# AuxBoard030624.net
KiCad netlist of a schematic drawn in Altium Designer
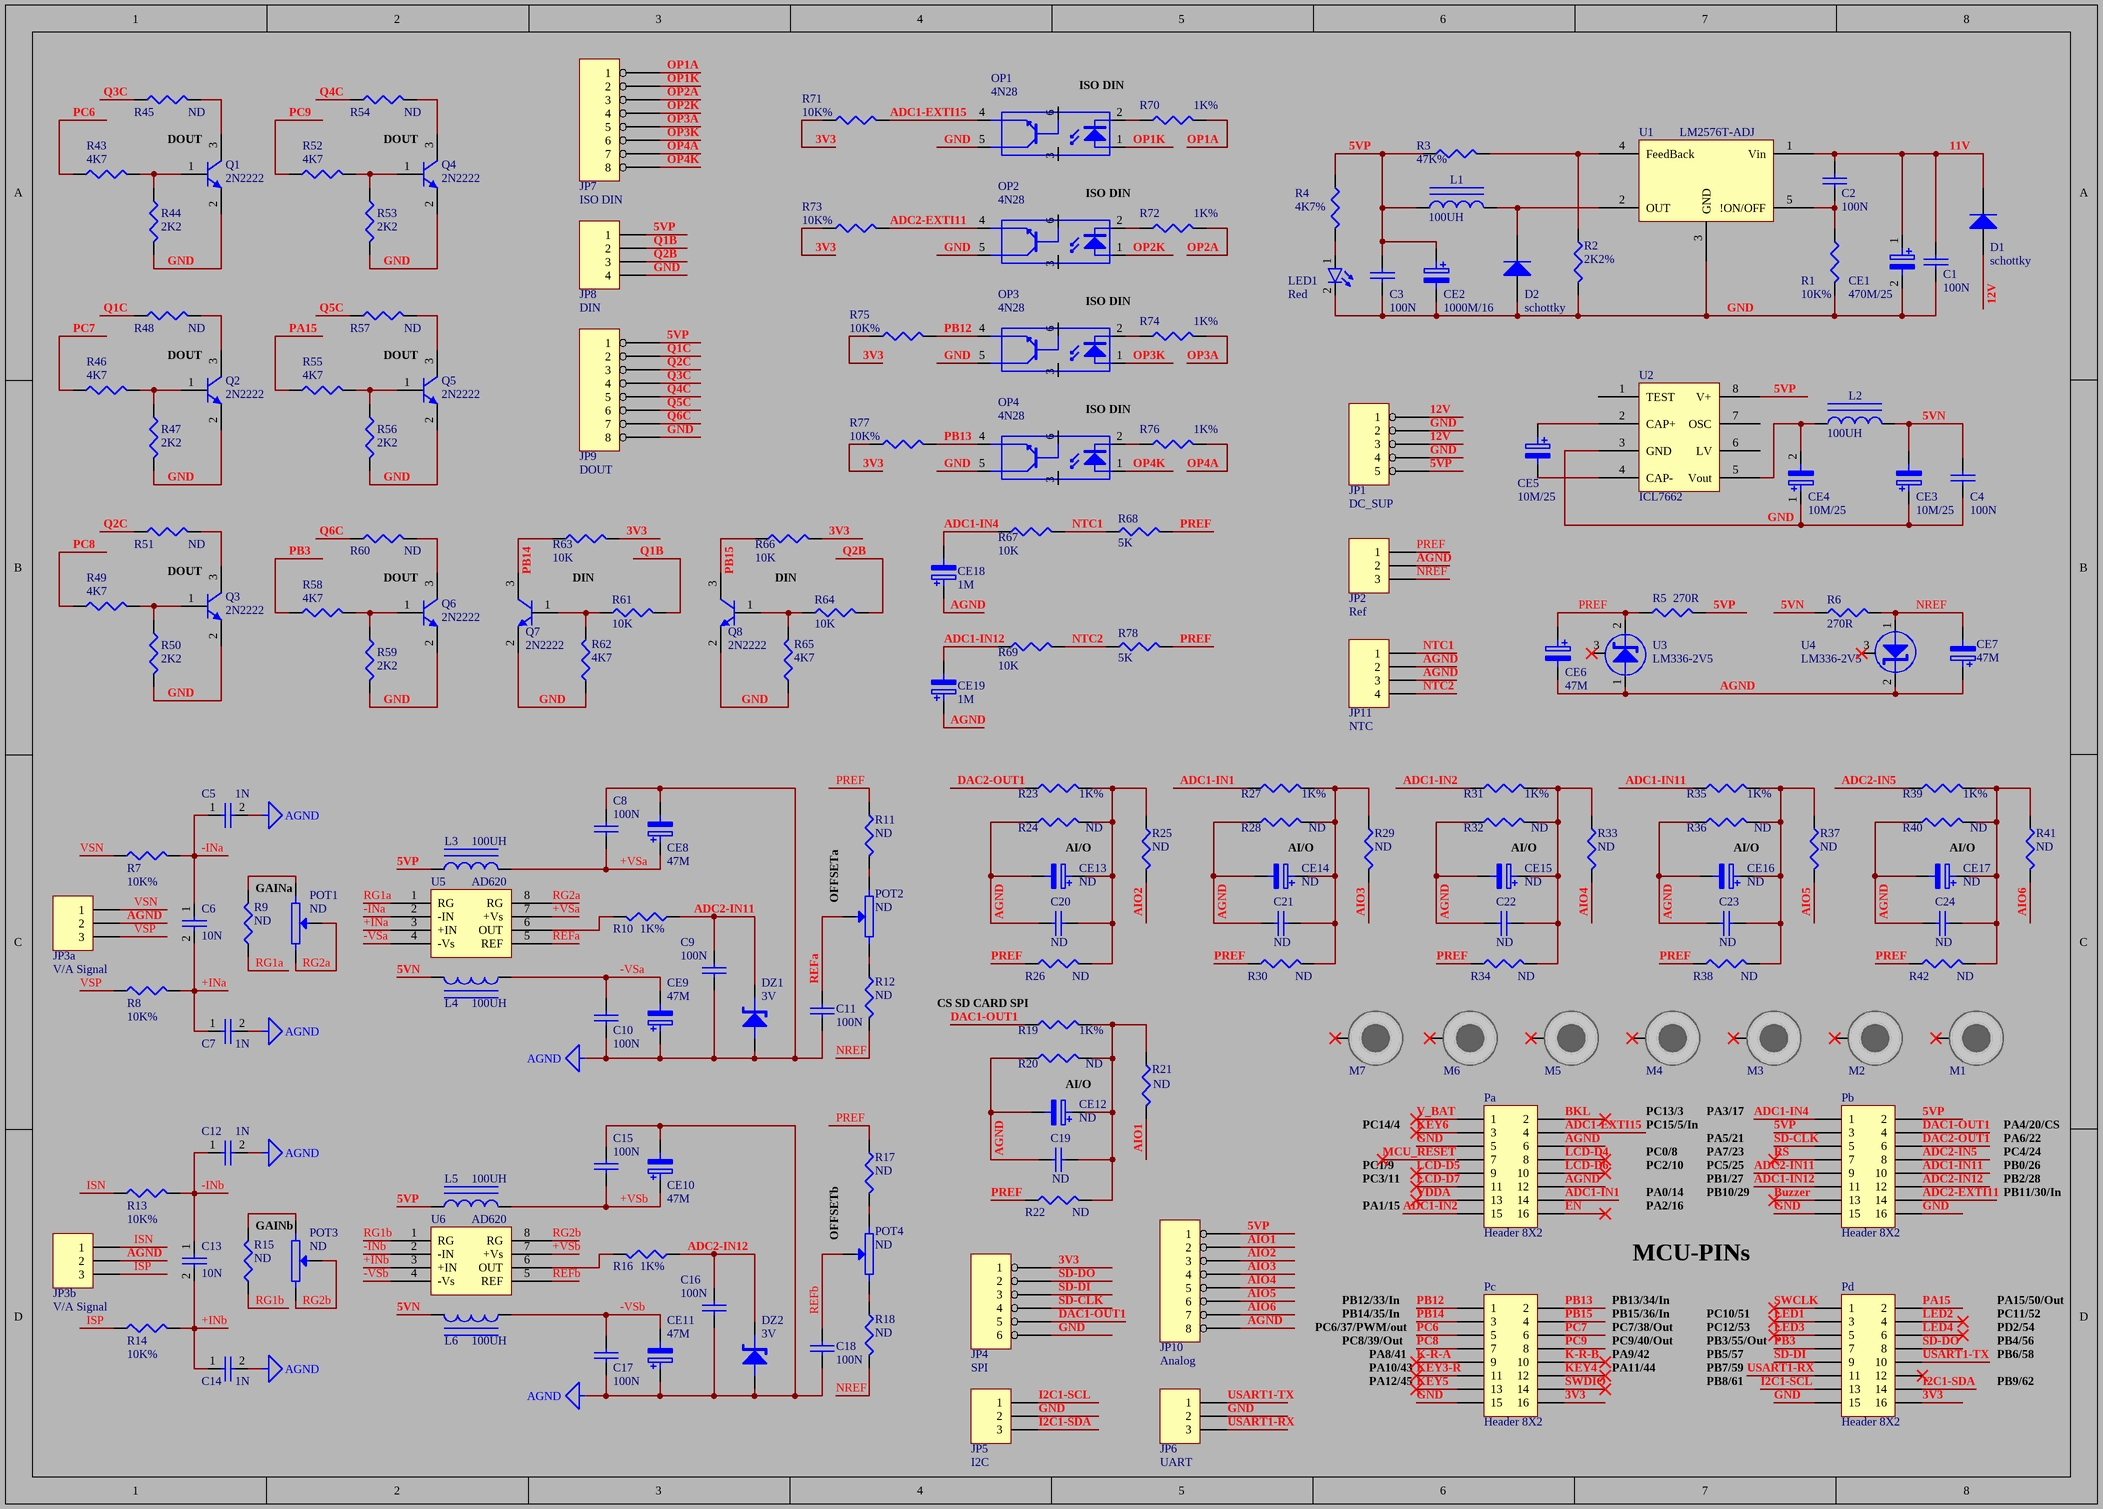
[diagram p0: AuxBoard030624.SchDoc]

(export (version "E")
  (design (tool "Eeschema 10.0.6"))
  (components
    (comp (ref "C1") (value "100N") (footprint "C2P") (libsource (lib "*") (part "C")))
    (comp (ref "C2") (value "100N") (footprint "SMD_CAP_1206.") (libsource (lib "*") (part "C")))
    (comp (ref "C3") (value "100N") (footprint "SMD_CAP_1206.") (libsource (lib "*") (part "C")))
    (comp (ref "C4") (value "100N") (footprint "SMD_CAP_1206.") (libsource (lib "*") (part "C")))
    (comp (ref "C5") (value "1N") (footprint "SMD_CAP_1206.") (libsource (lib "1402 Schlib 2020") (part "C")))
    (comp (ref "C6")
      (value "10N")
      (footprint "SMD_CAP_1206.")
      (libsource (lib "1402 Schlib 2020") (part "C"))
    )
    (comp (ref "C7") (value "1N") (footprint "SMD_CAP_1206.") (libsource (lib "1402 Schlib 2020") (part "C")))
    (comp (ref "C8")
      (value "100N")
      (footprint "SMD_CAP_1206.")
      (libsource (lib "1403 Schlib 2020") (part "C"))
    )
    (comp (ref "C9")
      (value "100N")
      (footprint "SMD_CAP_1206.")
      (libsource (lib "1403 Schlib 2020") (part "C"))
    )
    (comp (ref "C10")
      (value "100N")
      (footprint "SMD_CAP_1206.")
      (libsource (lib "1403 Schlib 2020") (part "C"))
    )
    (comp (ref "C11")
      (value "100N")
      (footprint "SMD_CAP_1206.")
      (libsource (lib "1403 Schlib 2020") (part "C"))
    )
    (comp (ref "C12")
      (value "1N")
      (footprint "SMD_CAP_1206.")
      (libsource (lib "1402 Schlib 2020") (part "C"))
    )
    (comp (ref "C13")
      (value "10N")
      (footprint "SMD_CAP_1206.")
      (libsource (lib "1402 Schlib 2020") (part "C"))
    )
    (comp (ref "C14")
      (value "1N")
      (footprint "SMD_CAP_1206.")
      (libsource (lib "1402 Schlib 2020") (part "C"))
    )
    (comp (ref "C15")
      (value "100N")
      (footprint "SMD_CAP_1206.")
      (libsource (lib "1403 Schlib 2020") (part "C"))
    )
    (comp (ref "C16")
      (value "100N")
      (footprint "SMD_CAP_1206.")
      (libsource (lib "1403 Schlib 2020") (part "C"))
    )
    (comp (ref "C17")
      (value "100N")
      (footprint "SMD_CAP_1206.")
      (libsource (lib "1403 Schlib 2020") (part "C"))
    )
    (comp (ref "C18")
      (value "100N")
      (footprint "SMD_CAP_1206.")
      (libsource (lib "1403 Schlib 2020") (part "C"))
    )
    (comp (ref "C19") (value "ND") (footprint "SMD_CAP_1206.") (libsource (lib "*") (part "C")))
    (comp (ref "C20") (value "ND") (footprint "SMD_CAP_1206.") (libsource (lib "*") (part "C")))
    (comp (ref "C21") (value "ND") (footprint "SMD_CAP_1206.") (libsource (lib "*") (part "C")))
    (comp (ref "C22") (value "ND") (footprint "SMD_CAP_1206.") (libsource (lib "*") (part "C")))
    (comp (ref "C23") (value "ND") (footprint "SMD_CAP_1206.") (libsource (lib "*") (part "C")))
    (comp (ref "C24") (value "ND") (footprint "SMD_CAP_1206.") (libsource (lib "*") (part "C")))
    (comp (ref "CE1") (value "470M/25") (footprint "CAP-E-6") (libsource (lib "*") (part "E")))
    (comp (ref "CE2") (value "1000M/16") (footprint "CAP-E-6") (libsource (lib "") (part "E_1")))
    (comp (ref "CE3") (value "10M/25") (footprint "CAP-E-3") (libsource (lib "") (part "E_1")))
    (comp (ref "CE4") (value "10M/25") (footprint "CAP-E-3") (libsource (lib "*") (part "E")))
    (comp (ref "CE5") (value "10M/25") (footprint "CAP-E-3") (libsource (lib "") (part "E_1")))
    (comp (ref "CE6") (value "47M") (footprint "CAP-E-4") (libsource (lib "1403 Schlib 2020") (part "E")))
    (comp (ref "CE7") (value "47M") (footprint "CAP-E-4") (libsource (lib "1403 Schlib 2020") (part "E")))
    (comp (ref "CE8") (value "47M") (footprint "CAP-E-4") (libsource (lib "1403 Schlib 2020") (part "E")))
    (comp (ref "CE9") (value "47M") (footprint "CAP-E-4") (libsource (lib "1403 Schlib 2020") (part "E")))
    (comp (ref "CE10") (value "47M") (footprint "CAP-E-4") (libsource (lib "1403 Schlib 2020") (part "E")))
    (comp (ref "CE11") (value "47M") (footprint "CAP-E-4") (libsource (lib "1403 Schlib 2020") (part "E")))
    (comp (ref "CE12") (value "ND") (footprint "CAP-E-3") (libsource (lib "") (part "E_1")))
    (comp (ref "CE13") (value "ND") (footprint "CAP-E-3") (libsource (lib "") (part "E_1")))
    (comp (ref "CE14") (value "ND") (footprint "CAP-E-3") (libsource (lib "") (part "E_1")))
    (comp (ref "CE15") (value "ND") (footprint "CAP-E-3") (libsource (lib "") (part "E_1")))
    (comp (ref "CE16") (value "ND") (footprint "CAP-E-3") (libsource (lib "") (part "E_1")))
    (comp (ref "CE17") (value "ND") (footprint "CAP-E-3") (libsource (lib "") (part "E_1")))
    (comp (ref "CE18") (value "1M") (footprint "CAP-E-2") (libsource (lib "") (part "E_1")))
    (comp (ref "CE19") (value "1M") (footprint "CAP-E-2") (libsource (lib "") (part "E_1")))
    (comp (ref "D1")
      (value "schottky")
      (footprint "SMA-M")
      (description "Default Diode")
      (fields (field (name "PUBLISHER") "Altium Limited"))
      (libsource (lib "Miscellaneous Devices") (part "Diode"))
    )
    (comp (ref "D2")
      (value "schottky")
      (footprint "SMA-M")
      (description "Default Diode")
      (fields (field (name "PUBLISHER") "Altium Limited"))
      (libsource (lib "Miscellaneous Devices") (part "Diode"))
    )
    (comp (ref "DZ1") (value "3V") (footprint "D4P") (libsource (lib "1402 Schlib 2020") (part "Z")))
    (comp (ref "DZ2") (value "3V") (footprint "D4P") (libsource (lib "1402 Schlib 2020") (part "Z")))
    (comp (ref "JP1")
      (value "DC_SUP")
      (footprint "dsip 5 right")
      (libsource (lib "1402 Schlib 2020") (part "HEADER 5"))
    )
    (comp (ref "JP2")
      (value "Ref")
      (footprint "dsip 3 right")
      (description "Header, 3-Pin")
      (fields (field (name "PUBLISHER") "Altium Limited"))
      (libsource (lib "1402 Schlib 2020") (part "Header 3"))
    )
    (comp (ref "JP3a")
      (value "V/A Signal")
      (footprint "dsip 3 right")
      (description "Header, 3-Pin")
      (fields (field (name "PUBLISHER") "Altium Limited"))
      (libsource (lib "1402 Schlib 2020") (part "Header 3"))
    )
    (comp (ref "JP3b")
      (value "V/A Signal")
      (footprint "dsip 3 right")
      (description "Header, 3-Pin")
      (fields (field (name "PUBLISHER") "Altium Limited"))
      (libsource (lib "1402 Schlib 2020") (part "Header 3"))
    )
    (comp (ref "JP4")
      (value "SPI")
      (footprint "SIP 6 Right")
      (libsource (lib "1402 Schlib 2020") (part "HEADER 6"))
    )
    (comp (ref "JP5")
      (value "I2C")
      (footprint "SIP 3 Right")
      (description "Header, 3-Pin")
      (fields (field (name "PUBLISHER") "Altium Limited"))
      (libsource (lib "1402 Schlib 2020") (part "Header 3"))
    )
    (comp (ref "JP6")
      (value "UART")
      (footprint "SIP 3 Right")
      (description "Header, 3-Pin")
      (fields (field (name "PUBLISHER") "Altium Limited"))
      (libsource (lib "1402 Schlib 2020") (part "Header 3"))
    )
    (comp (ref "JP7")
      (value "ISO DIN")
      (footprint "dsip 8 right")
      (libsource (lib "1402 Schlib 2020") (part "HEADER 8"))
    )
    (comp (ref "JP8")
      (value "DIN")
      (footprint "dsip 4 right")
      (description "Header, 4-Pin")
      (fields (field (name "PUBLISHER") "Altium Limited"))
      (libsource (lib "1402 Schlib 2020") (part "Header 4"))
    )
    (comp (ref "JP9")
      (value "DOUT")
      (footprint "dsip 8 right")
      (libsource (lib "1402 Schlib 2020") (part "HEADER 8"))
    )
    (comp (ref "JP10")
      (value "Analog")
      (footprint "dsip 8 right")
      (libsource (lib "1402 Schlib 2020") (part "HEADER 8"))
    )
    (comp (ref "JP11")
      (value "NTC")
      (footprint "dsip 4 right")
      (description "Header, 4-Pin")
      (fields (field (name "PUBLISHER") "Altium Limited"))
      (libsource (lib "1402 Schlib 2020") (part "Header 4"))
    )
    (comp (ref "L1") (value "100UH") (footprint "INDUCTOR-ylw") (libsource (lib "*") (part "INDUCTOR IRON")))
    (comp (ref "L2") (value "100UH") (footprint "r4p") (libsource (lib "*") (part "INDUCTOR IRON")))
    (comp (ref "L3") (value "100UH") (footprint "r4p") (libsource (lib "*") (part "INDUCTOR IRON")))
    (comp (ref "L4") (value "100UH") (footprint "r4p") (libsource (lib "") (part "INDUCTOR IRON_1")))
    (comp (ref "L5") (value "100UH") (footprint "r4p") (libsource (lib "*") (part "INDUCTOR IRON")))
    (comp (ref "L6") (value "100UH") (footprint "r4p") (libsource (lib "") (part "INDUCTOR IRON_1")))
    (comp (ref "LED1")
      (value "Red")
      (footprint "LED_SMD_1206")
      (description "LED")
      (fields (field (name "COLOR") "Red") (field (name "DESIGNER") "Saeid Jorablo"))
      (libsource (lib "My Library") (part "LED"))
    )
    (comp (ref "M1")
      (value "Comment")
      (footprint "Stud-hole")
      (description "SCREW mouting, M1.6, 1.6mm diameter and 3.2mm PanHead")
      (libsource (lib "DotexGroup_LIB") (part "SCMH_M1P6"))
    )
    (comp (ref "M2")
      (value "Comment")
      (footprint "Stud-hole")
      (description "SCREW mouting, M1.6, 1.6mm diameter and 3.2mm PanHead")
      (libsource (lib "DotexGroup_LIB") (part "SCMH_M1P6"))
    )
    (comp (ref "M3")
      (value "Comment")
      (footprint "Stud-hole")
      (description "SCREW mouting, M1.6, 1.6mm diameter and 3.2mm PanHead")
      (libsource (lib "DotexGroup_LIB") (part "SCMH_M1P6"))
    )
    (comp (ref "M4")
      (value "Comment")
      (footprint "Stud-hole")
      (description "SCREW mouting, M1.6, 1.6mm diameter and 3.2mm PanHead")
      (libsource (lib "DotexGroup_LIB") (part "SCMH_M1P6"))
    )
    (comp (ref "M5")
      (value "Comment")
      (footprint "Stud-hole")
      (description "SCREW mouting, M1.6, 1.6mm diameter and 3.2mm PanHead")
      (libsource (lib "DotexGroup_LIB") (part "SCMH_M1P6"))
    )
    (comp (ref "M6")
      (value "Comment")
      (footprint "Stud-hole")
      (description "SCREW mouting, M1.6, 1.6mm diameter and 3.2mm PanHead")
      (libsource (lib "DotexGroup_LIB") (part "SCMH_M1P6"))
    )
    (comp (ref "M7")
      (value "Comment")
      (footprint "Stud-hole")
      (description "SCREW mouting, M1.6, 1.6mm diameter and 3.2mm PanHead")
      (libsource (lib "DotexGroup_LIB") (part "SCMH_M1P6"))
    )
    (comp (ref "OP1")
      (value "4N28")
      (footprint "DIP6")
      (libsource (lib "1402 Schlib 2020") (part "OPTODIP6"))
    )
    (comp (ref "OP2")
      (value "4N28")
      (footprint "DIP6")
      (libsource (lib "1402 Schlib 2020") (part "OPTODIP6"))
    )
    (comp (ref "OP3")
      (value "4N28")
      (footprint "DIP6")
      (libsource (lib "1402 Schlib 2020") (part "OPTODIP6"))
    )
    (comp (ref "OP4")
      (value "4N28")
      (footprint "DIP6")
      (libsource (lib "1402 Schlib 2020") (part "OPTODIP6"))
    )
    (comp (ref "Pa")
      (value "Header 8X2")
      (footprint "HDR2X8")
      (description "Header, 8-Pin, Dual row")
      (fields (field (name "PUBLISHER") "Altium Limited"))
      (libsource (lib "Miscellaneous Connectors") (part "Header 8X2"))
    )
    (comp (ref "Pb")
      (value "Header 8X2")
      (footprint "HDR2X8")
      (description "Header, 8-Pin, Dual row")
      (fields (field (name "PUBLISHER") "Altium Limited"))
      (libsource (lib "Miscellaneous Connectors") (part "Header 8X2"))
    )
    (comp (ref "Pc")
      (value "Header 8X2")
      (footprint "HDR2X8")
      (description "Header, 8-Pin, Dual row")
      (fields (field (name "PUBLISHER") "Altium Limited"))
      (libsource (lib "Miscellaneous Connectors") (part "Header 8X2"))
    )
    (comp (ref "Pd")
      (value "Header 8X2")
      (footprint "HDR2X8")
      (description "Header, 8-Pin, Dual row")
      (fields (field (name "PUBLISHER") "Altium Limited"))
      (libsource (lib "Miscellaneous Connectors") (part "Header 8X2"))
    )
    (comp (ref "POT1")
      (value "ND")
      (footprint "pot multi turn")
      (libsource (lib "1402 Schlib 2020") (part "POT2"))
    )
    (comp (ref "POT2")
      (value "ND")
      (footprint "pot multi turn")
      (libsource (lib "1402 Schlib 2020") (part "POT2"))
    )
    (comp (ref "POT3")
      (value "ND")
      (footprint "pot multi turn")
      (libsource (lib "1402 Schlib 2020") (part "POT2"))
    )
    (comp (ref "POT4")
      (value "ND")
      (footprint "pot multi turn")
      (libsource (lib "1402 Schlib 2020") (part "POT2"))
    )
    (comp (ref "Q1")
      (value "2N2222")
      (footprint "2N2222")
      (description "NPN")
      (fields (field (name "PUBLISHER") "Altium Limited"))
      (libsource (lib "1402 Schlib 2020") (part "1FW"))
    )
    (comp (ref "Q2")
      (value "2N2222")
      (footprint "2N2222")
      (description "NPN")
      (fields (field (name "PUBLISHER") "Altium Limited"))
      (libsource (lib "1402 Schlib 2020") (part "1FW"))
    )
    (comp (ref "Q3")
      (value "2N2222")
      (footprint "2N2222")
      (description "NPN")
      (fields (field (name "PUBLISHER") "Altium Limited"))
      (libsource (lib "1402 Schlib 2020") (part "1FW"))
    )
    (comp (ref "Q4")
      (value "2N2222")
      (footprint "2N2222")
      (description "NPN")
      (fields (field (name "PUBLISHER") "Altium Limited"))
      (libsource (lib "1402 Schlib 2020") (part "1FW"))
    )
    (comp (ref "Q5")
      (value "2N2222")
      (footprint "2N2222")
      (description "NPN")
      (fields (field (name "PUBLISHER") "Altium Limited"))
      (libsource (lib "1402 Schlib 2020") (part "1FW"))
    )
    (comp (ref "Q6")
      (value "2N2222")
      (footprint "2N2222")
      (description "NPN")
      (fields (field (name "PUBLISHER") "Altium Limited"))
      (libsource (lib "1402 Schlib 2020") (part "1FW"))
    )
    (comp (ref "Q7")
      (value "2N2222")
      (footprint "2N2222")
      (description "NPN")
      (fields (field (name "PUBLISHER") "Altium Limited"))
      (libsource (lib "1402 Schlib 2020") (part "1FW"))
    )
    (comp (ref "Q8")
      (value "2N2222")
      (footprint "2N2222")
      (description "NPN")
      (fields (field (name "PUBLISHER") "Altium Limited"))
      (libsource (lib "1402 Schlib 2020") (part "1FW"))
    )
    (comp (ref "R1") (value "10K%") (footprint "RES_1206") (libsource (lib "*") (part "R")))
    (comp (ref "R2") (value "2K2%") (footprint "RES_1206") (libsource (lib "*") (part "R")))
    (comp (ref "R3") (value "47K%") (footprint "RES_1206") (libsource (lib "*") (part "R")))
    (comp (ref "R4") (value "4K7%") (footprint "RES_1206") (libsource (lib "*") (part "R")))
    (comp (ref "R5") (value "270R") (footprint "RES_1206") (libsource (lib "*") (part "R")))
    (comp (ref "R6") (value "270R") (footprint "RES_1206") (libsource (lib "*") (part "R")))
    (comp (ref "R7") (value "10K%") (footprint "R4P") (libsource (lib "*") (part "R")))
    (comp (ref "R8") (value "10K%") (footprint "R4P") (libsource (lib "*") (part "R")))
    (comp (ref "R9") (value "ND") (footprint "R4P") (libsource (lib "*") (part "R")))
    (comp (ref "R10") (value "1K%") (footprint "RES_1206") (libsource (lib "*") (part "R")))
    (comp (ref "R11") (value "ND") (footprint "RES_1206") (libsource (lib "*") (part "R")))
    (comp (ref "R12") (value "ND") (footprint "RES_1206") (libsource (lib "*") (part "R")))
    (comp (ref "R13") (value "10K%") (footprint "R4P") (libsource (lib "*") (part "R")))
    (comp (ref "R14") (value "10K%") (footprint "R4P") (libsource (lib "*") (part "R")))
    (comp (ref "R15") (value "ND") (footprint "R4P") (libsource (lib "*") (part "R")))
    (comp (ref "R16") (value "1K%") (footprint "RES_1206") (libsource (lib "*") (part "R")))
    (comp (ref "R17") (value "ND") (footprint "RES_1206") (libsource (lib "*") (part "R")))
    (comp (ref "R18") (value "ND") (footprint "RES_1206") (libsource (lib "*") (part "R")))
    (comp (ref "R19") (value "1K%") (footprint "RES_1206") (libsource (lib "*") (part "R")))
    (comp (ref "R20") (value "ND") (footprint "RES_1206") (libsource (lib "*") (part "R")))
    (comp (ref "R21") (value "ND") (footprint "RES_1206") (libsource (lib "*") (part "R")))
    (comp (ref "R22") (value "ND") (footprint "RES_1206") (libsource (lib "*") (part "R")))
    (comp (ref "R23") (value "1K%") (footprint "RES_1206") (libsource (lib "*") (part "R")))
    (comp (ref "R24") (value "ND") (footprint "RES_1206") (libsource (lib "*") (part "R")))
    (comp (ref "R25") (value "ND") (footprint "RES_1206") (libsource (lib "*") (part "R")))
    (comp (ref "R26") (value "ND") (footprint "RES_1206") (libsource (lib "*") (part "R")))
    (comp (ref "R27") (value "1K%") (footprint "RES_1206") (libsource (lib "*") (part "R")))
    (comp (ref "R28") (value "ND") (footprint "RES_1206") (libsource (lib "*") (part "R")))
    (comp (ref "R29") (value "ND") (footprint "RES_1206") (libsource (lib "*") (part "R")))
    (comp (ref "R30") (value "ND") (footprint "RES_1206") (libsource (lib "*") (part "R")))
    (comp (ref "R31") (value "1K%") (footprint "RES_1206") (libsource (lib "*") (part "R")))
    (comp (ref "R32") (value "ND") (footprint "RES_1206") (libsource (lib "*") (part "R")))
    (comp (ref "R33") (value "ND") (footprint "RES_1206") (libsource (lib "*") (part "R")))
    (comp (ref "R34") (value "ND") (footprint "RES_1206") (libsource (lib "*") (part "R")))
    (comp (ref "R35") (value "1K%") (footprint "RES_1206") (libsource (lib "*") (part "R")))
    (comp (ref "R36") (value "ND") (footprint "RES_1206") (libsource (lib "*") (part "R")))
    (comp (ref "R37") (value "ND") (footprint "RES_1206") (libsource (lib "*") (part "R")))
    (comp (ref "R38") (value "ND") (footprint "RES_1206") (libsource (lib "*") (part "R")))
    (comp (ref "R39") (value "1K%") (footprint "RES_1206") (libsource (lib "*") (part "R")))
    (comp (ref "R40") (value "ND") (footprint "RES_1206") (libsource (lib "*") (part "R")))
    (comp (ref "R41") (value "ND") (footprint "RES_1206") (libsource (lib "*") (part "R")))
    (comp (ref "R42") (value "ND") (footprint "RES_1206") (libsource (lib "*") (part "R")))
    (comp (ref "R43") (value "4K7") (footprint "RES_1206") (libsource (lib "*") (part "R")))
    (comp (ref "R44") (value "2K2") (footprint "RES_1206") (libsource (lib "*") (part "R")))
    (comp (ref "R45") (value "ND") (footprint "RES_1206") (libsource (lib "*") (part "R")))
    (comp (ref "R46") (value "4K7") (footprint "RES_1206") (libsource (lib "*") (part "R")))
    (comp (ref "R47") (value "2K2") (footprint "RES_1206") (libsource (lib "*") (part "R")))
    (comp (ref "R48") (value "ND") (footprint "RES_1206") (libsource (lib "*") (part "R")))
    (comp (ref "R49") (value "4K7") (footprint "RES_1206") (libsource (lib "*") (part "R")))
    (comp (ref "R50") (value "2K2") (footprint "RES_1206") (libsource (lib "*") (part "R")))
    (comp (ref "R51") (value "ND") (footprint "RES_1206") (libsource (lib "*") (part "R")))
    (comp (ref "R52") (value "4K7") (footprint "RES_1206") (libsource (lib "*") (part "R")))
    (comp (ref "R53") (value "2K2") (footprint "RES_1206") (libsource (lib "*") (part "R")))
    (comp (ref "R54") (value "ND") (footprint "RES_1206") (libsource (lib "*") (part "R")))
    (comp (ref "R55") (value "4K7") (footprint "RES_1206") (libsource (lib "*") (part "R")))
    (comp (ref "R56") (value "2K2") (footprint "RES_1206") (libsource (lib "*") (part "R")))
    (comp (ref "R57") (value "ND") (footprint "RES_1206") (libsource (lib "*") (part "R")))
    (comp (ref "R58") (value "4K7") (footprint "RES_1206") (libsource (lib "*") (part "R")))
    (comp (ref "R59") (value "2K2") (footprint "RES_1206") (libsource (lib "*") (part "R")))
    (comp (ref "R60") (value "ND") (footprint "RES_1206") (libsource (lib "*") (part "R")))
    (comp (ref "R61") (value "10K") (footprint "RES_1206") (libsource (lib "*") (part "R")))
    (comp (ref "R62") (value "4K7") (footprint "RES_1206") (libsource (lib "*") (part "R")))
    (comp (ref "R63") (value "10K") (footprint "RES_1206") (libsource (lib "*") (part "R")))
    (comp (ref "R64") (value "10K") (footprint "RES_1206") (libsource (lib "*") (part "R")))
    (comp (ref "R65") (value "4K7") (footprint "RES_1206") (libsource (lib "*") (part "R")))
    (comp (ref "R66") (value "10K") (footprint "RES_1206") (libsource (lib "*") (part "R")))
    (comp (ref "R67") (value "10K") (footprint "RES_1206") (libsource (lib "*") (part "R")))
    (comp (ref "R68") (value "5K") (footprint "RES_1206") (libsource (lib "*") (part "R")))
    (comp (ref "R69") (value "10K") (footprint "RES_1206") (libsource (lib "*") (part "R")))
    (comp (ref "R70") (value "1K%") (footprint "RES_1206") (libsource (lib "*") (part "R")))
    (comp (ref "R71") (value "10K%") (footprint "RES_1206") (libsource (lib "*") (part "R")))
    (comp (ref "R72") (value "1K%") (footprint "RES_1206") (libsource (lib "*") (part "R")))
    (comp (ref "R73") (value "10K%") (footprint "RES_1206") (libsource (lib "*") (part "R")))
    (comp (ref "R74") (value "1K%") (footprint "RES_1206") (libsource (lib "*") (part "R")))
    (comp (ref "R75") (value "10K%") (footprint "RES_1206") (libsource (lib "*") (part "R")))
    (comp (ref "R76") (value "1K%") (footprint "RES_1206") (libsource (lib "*") (part "R")))
    (comp (ref "R77") (value "10K%") (footprint "RES_1206") (libsource (lib "*") (part "R")))
    (comp (ref "R78") (value "5K") (footprint "RES_1206") (libsource (lib "*") (part "R")))
    (comp (ref "U1") (value "LM2576T-ADJ") (footprint "D2PACK_TO263-5") (libsource (lib "*") (part "LM2576")))
    (comp (ref "U2")
      (value "ICL7662")
      (footprint "DIP8")
      (libsource (lib "1402 Schlib 2020") (part "ICL7662"))
    )
    (comp (ref "U3")
      (value "LM336-2V5")
      (footprint "lm336")
      (libsource (lib "1403 Schlib 2020") (part "LM336"))
    )
    (comp (ref "U4")
      (value "LM336-2V5")
      (footprint "lm336")
      (libsource (lib "1403 Schlib 2020") (part "LM336"))
    )
    (comp (ref "U5") (value "AD620") (footprint "DIP8") (libsource (lib "1402 Schlib 2020") (part "AD620")))
    (comp (ref "U6") (value "AD620") (footprint "DIP8") (libsource (lib "1402 Schlib 2020") (part "AD620")))
  )
  (nets
    (net (code "1") (name "/+INa") (class "Default")
      (node (ref "C6") (pin "2") (pintype "passive"))
      (node (ref "C7") (pin "1") (pintype "passive"))
      (node (ref "R8") (pin "2") (pintype "passive"))
      (node (ref "U5") (pin "3") (pinfunction "+IN_3") (pintype "passive"))
    )
    (net (code "2") (name "/+INb") (class "Default")
      (node (ref "C13") (pin "2") (pintype "passive"))
      (node (ref "C14") (pin "1") (pintype "passive"))
      (node (ref "R14") (pin "2") (pintype "passive"))
      (node (ref "U6") (pin "3") (pinfunction "+IN_3") (pintype "passive"))
    )
    (net (code "3") (name "/+VSa") (class "Default")
      (node (ref "C8") (pin "2") (pintype "passive"))
      (node (ref "CE8") (pin "1") (pintype "passive"))
      (node (ref "L3") (pin "2") (pinfunction "2_2") (pintype "passive"))
      (node (ref "U5") (pin "7") (pinfunction "+Vs_7") (pintype "passive"))
    )
    (net (code "4") (name "/+VSb") (class "Default")
      (node (ref "C15") (pin "2") (pintype "passive"))
      (node (ref "CE10") (pin "1") (pintype "passive"))
      (node (ref "L5") (pin "2") (pinfunction "2_2") (pintype "passive"))
      (node (ref "U6") (pin "7") (pinfunction "+Vs_7") (pintype "passive"))
    )
    (net (code "5") (name "/-INa") (class "Default")
      (node (ref "C5") (pin "1") (pintype "passive"))
      (node (ref "C6") (pin "1") (pintype "passive"))
      (node (ref "R7") (pin "2") (pintype "passive"))
      (node (ref "U5") (pin "2") (pinfunction "-IN_2") (pintype "passive"))
    )
    (net (code "6") (name "/-INb") (class "Default")
      (node (ref "C12") (pin "1") (pintype "passive"))
      (node (ref "C13") (pin "1") (pintype "passive"))
      (node (ref "R13") (pin "2") (pintype "passive"))
      (node (ref "U6") (pin "2") (pinfunction "-IN_2") (pintype "passive"))
    )
    (net (code "7") (name "/-VSa") (class "Default")
      (node (ref "C10") (pin "1") (pintype "passive"))
      (node (ref "CE9") (pin "2") (pintype "passive"))
      (node (ref "L4") (pin "2") (pinfunction "2_2") (pintype "passive"))
      (node (ref "U5") (pin "4") (pinfunction "-Vs_4") (pintype "passive"))
    )
    (net (code "8") (name "/-VSb") (class "Default")
      (node (ref "C17") (pin "1") (pintype "passive"))
      (node (ref "CE11") (pin "2") (pintype "passive"))
      (node (ref "L6") (pin "2") (pinfunction "2_2") (pintype "passive"))
      (node (ref "U6") (pin "4") (pinfunction "-Vs_4") (pintype "passive"))
    )
    (net (code "9") (name "/3V3") (class "Default")
      (node (ref "JP4") (pin "1") (pinfunction "1_1") (pintype "passive"))
      (node (ref "Pc") (pin "16") (pinfunction "16_16") (pintype "passive"))
      (node (ref "Pd") (pin "16") (pinfunction "16_16") (pintype "passive"))
      (node (ref "R63") (pin "1") (pintype "passive"))
      (node (ref "R66") (pin "1") (pintype "passive"))
      (node (ref "R71") (pin "2") (pintype "passive"))
      (node (ref "R73") (pin "2") (pintype "passive"))
      (node (ref "R75") (pin "2") (pintype "passive"))
      (node (ref "R77") (pin "2") (pintype "passive"))
    )
    (net (code "10") (name "/5VN") (class "Default")
      (node (ref "C4") (pin "1") (pintype "passive"))
      (node (ref "CE3") (pin "2") (pintype "passive"))
      (node (ref "L2") (pin "2") (pinfunction "2_2") (pintype "passive"))
      (node (ref "L4") (pin "1") (pinfunction "1_1") (pintype "passive"))
      (node (ref "L6") (pin "1") (pinfunction "1_1") (pintype "passive"))
      (node (ref "R6") (pin "2") (pintype "passive"))
    )
    (net (code "11") (name "/5VP") (class "Default")
      (node (ref "C3") (pin "1") (pintype "passive"))
      (node (ref "CE2") (pin "1") (pintype "passive"))
      (node (ref "JP1") (pin "5") (pinfunction "5_5") (pintype "passive"))
      (node (ref "JP10") (pin "1") (pinfunction "1_1") (pintype "passive"))
      (node (ref "JP8") (pin "1") (pinfunction "1_1") (pintype "passive"))
      (node (ref "JP9") (pin "1") (pinfunction "1_1") (pintype "passive"))
      (node (ref "L1") (pin "1") (pinfunction "1_1") (pintype "passive"))
      (node (ref "L3") (pin "1") (pinfunction "1_1") (pintype "passive"))
      (node (ref "L5") (pin "1") (pinfunction "1_1") (pintype "passive"))
      (node (ref "Pb") (pin "2") (pinfunction "2_2") (pintype "passive"))
      (node (ref "Pb") (pin "3") (pinfunction "3_3") (pintype "passive"))
      (node (ref "R3") (pin "1") (pintype "passive"))
      (node (ref "R4") (pin "1") (pintype "passive"))
      (node (ref "R5") (pin "2") (pintype "passive"))
      (node (ref "U2") (pin "8") (pinfunction "V+_8") (pintype "passive"))
    )
    (net (code "12") (name "/11V") (class "Default")
      (node (ref "C1") (pin "1") (pintype "passive"))
      (node (ref "C2") (pin "1") (pintype "passive"))
      (node (ref "CE1") (pin "1") (pintype "passive"))
      (node (ref "D1") (pin "2") (pinfunction "K_2") (pintype "passive"))
      (node (ref "U1") (pin "1") (pinfunction "Vin_1") (pintype "passive"))
    )
    (net (code "13") (name "/12V") (class "Default")
      (node (ref "D1") (pin "1") (pinfunction "A_1") (pintype "passive"))
      (node (ref "JP1") (pin "1") (pinfunction "1_1") (pintype "passive"))
      (node (ref "JP1") (pin "3") (pinfunction "3_3") (pintype "passive"))
    )
    (net (code "14") (name "/ADC1-EXTI15") (class "Default")
      (node (ref "OP1") (pin "4") (pinfunction "E_4") (pintype "passive"))
      (node (ref "Pa") (pin "4") (pinfunction "4_4") (pintype "passive"))
      (node (ref "R71") (pin "1") (pintype "passive"))
    )
    (net (code "15") (name "/ADC1-IN1") (class "Default")
      (node (ref "Pa") (pin "14") (pinfunction "14_14") (pintype "passive"))
      (node (ref "R27") (pin "1") (pintype "passive"))
    )
    (net (code "16") (name "/ADC1-IN2") (class "Default")
      (node (ref "Pa") (pin "15") (pinfunction "15_15") (pintype "passive"))
      (node (ref "R31") (pin "1") (pintype "passive"))
    )
    (net (code "17") (name "/ADC1-IN4") (class "Default")
      (node (ref "CE18") (pin "2") (pintype "passive"))
      (node (ref "Pb") (pin "1") (pinfunction "1_1") (pintype "passive"))
      (node (ref "R67") (pin "2") (pintype "passive"))
    )
    (net (code "18") (name "/ADC1-IN11") (class "Default")
      (node (ref "Pb") (pin "10") (pinfunction "10_10") (pintype "passive"))
      (node (ref "R35") (pin "1") (pintype "passive"))
    )
    (net (code "19") (name "/ADC1-IN12") (class "Default")
      (node (ref "CE19") (pin "2") (pintype "passive"))
      (node (ref "Pb") (pin "11") (pinfunction "11_11") (pintype "passive"))
      (node (ref "R69") (pin "2") (pintype "passive"))
    )
    (net (code "20") (name "/ADC2-EXTI11") (class "Default")
      (node (ref "OP2") (pin "4") (pinfunction "E_4") (pintype "passive"))
      (node (ref "Pb") (pin "14") (pinfunction "14_14") (pintype "passive"))
      (node (ref "R73") (pin "1") (pintype "passive"))
    )
    (net (code "21") (name "/ADC2-IN5") (class "Default")
      (node (ref "Pb") (pin "8") (pinfunction "8_8") (pintype "passive"))
      (node (ref "R39") (pin "1") (pintype "passive"))
    )
    (net (code "22") (name "/ADC2-IN11") (class "Default")
      (node (ref "C9") (pin "1") (pintype "passive"))
      (node (ref "DZ1") (pin "2") (pinfunction "K_2") (pintype "passive"))
      (node (ref "Pb") (pin "9") (pinfunction "9_9") (pintype "passive"))
      (node (ref "R10") (pin "1") (pintype "passive"))
    )
    (net (code "23") (name "/ADC2-IN12") (class "Default")
      (node (ref "C16") (pin "1") (pintype "passive"))
      (node (ref "DZ2") (pin "2") (pinfunction "K_2") (pintype "passive"))
      (node (ref "Pb") (pin "12") (pinfunction "12_12") (pintype "passive"))
      (node (ref "R16") (pin "1") (pintype "passive"))
    )
    (net (code "24") (name "/AIO1") (class "Default")
      (node (ref "JP10") (pin "2") (pinfunction "2_2") (pintype "passive"))
      (node (ref "R21") (pin "2") (pintype "passive"))
    )
    (net (code "25") (name "/AIO2") (class "Default")
      (node (ref "JP10") (pin "3") (pinfunction "3_3") (pintype "passive"))
      (node (ref "R25") (pin "2") (pintype "passive"))
    )
    (net (code "26") (name "/AIO3") (class "Default")
      (node (ref "JP10") (pin "4") (pinfunction "4_4") (pintype "passive"))
      (node (ref "R29") (pin "2") (pintype "passive"))
    )
    (net (code "27") (name "/AIO4") (class "Default")
      (node (ref "JP10") (pin "5") (pinfunction "5_5") (pintype "passive"))
      (node (ref "R33") (pin "2") (pintype "passive"))
    )
    (net (code "28") (name "/AIO5") (class "Default")
      (node (ref "JP10") (pin "6") (pinfunction "6_6") (pintype "passive"))
      (node (ref "R37") (pin "2") (pintype "passive"))
    )
    (net (code "29") (name "/AIO6") (class "Default")
      (node (ref "JP10") (pin "7") (pinfunction "7_7") (pintype "passive"))
      (node (ref "R41") (pin "2") (pintype "passive"))
    )
    (net (code "30") (name "/BKL") (class "Default")
      (node (ref "Pa") (pin "2") (pinfunction "2_2") (pintype "passive+no_connect"))
    )
    (net (code "31") (name "/Buzzer") (class "Default")
      (node (ref "Pb") (pin "13") (pinfunction "13_13") (pintype "passive+no_connect"))
    )
    (net (code "32") (name "/DAC1-OUT1") (class "Default")
      (node (ref "JP4") (pin "5") (pinfunction "5_5") (pintype "passive"))
      (node (ref "Pb") (pin "4") (pinfunction "4_4") (pintype "passive"))
      (node (ref "R19") (pin "1") (pintype "passive"))
    )
    (net (code "33") (name "/DAC2-OUT1") (class "Default")
      (node (ref "Pb") (pin "6") (pinfunction "6_6") (pintype "passive"))
      (node (ref "R23") (pin "1") (pintype "passive"))
    )
    (net (code "34") (name "/EN") (class "Default")
      (node (ref "Pa") (pin "16") (pinfunction "16_16") (pintype "passive+no_connect"))
    )
    (net (code "35") (name "/GND") (class "Default")
      (node (ref "C1") (pin "2") (pintype "passive"))
      (node (ref "C3") (pin "2") (pintype "passive"))
      (node (ref "C4") (pin "2") (pintype "passive"))
      (node (ref "CE1") (pin "2") (pintype "passive"))
      (node (ref "CE2") (pin "2") (pintype "passive"))
      (node (ref "CE3") (pin "1") (pintype "passive"))
      (node (ref "CE4") (pin "1") (pintype "passive"))
      (node (ref "D2") (pin "1") (pinfunction "A_1") (pintype "passive"))
      (node (ref "JP1") (pin "2") (pinfunction "2_2") (pintype "passive"))
      (node (ref "JP1") (pin "4") (pinfunction "4_4") (pintype "passive"))
      (node (ref "JP4") (pin "6") (pinfunction "6_6") (pintype "passive"))
      (node (ref "JP5") (pin "2") (pinfunction "2_2") (pintype "passive"))
      (node (ref "JP6") (pin "2") (pinfunction "2_2") (pintype "passive"))
      (node (ref "JP8") (pin "4") (pinfunction "4_4") (pintype "passive"))
      (node (ref "JP9") (pin "8") (pinfunction "8_8") (pintype "passive"))
      (node (ref "LED1") (pin "2") (pinfunction "K_2") (pintype "passive"))
      (node (ref "OP1") (pin "5") (pinfunction "C_5") (pintype "passive"))
      (node (ref "OP2") (pin "5") (pinfunction "C_5") (pintype "passive"))
      (node (ref "OP3") (pin "5") (pinfunction "C_5") (pintype "passive"))
      (node (ref "OP4") (pin "5") (pinfunction "C_5") (pintype "passive"))
      (node (ref "Pa") (pin "5") (pinfunction "5_5") (pintype "passive"))
      (node (ref "Pb") (pin "15") (pinfunction "15_15") (pintype "passive"))
      (node (ref "Pb") (pin "16") (pinfunction "16_16") (pintype "passive"))
      (node (ref "Pc") (pin "15") (pinfunction "15_15") (pintype "passive"))
      (node (ref "Pd") (pin "15") (pinfunction "15_15") (pintype "passive"))
      (node (ref "Q1") (pin "2") (pinfunction "E_2") (pintype "passive"))
      (node (ref "Q2") (pin "2") (pinfunction "E_2") (pintype "passive"))
      (node (ref "Q3") (pin "2") (pinfunction "E_2") (pintype "passive"))
      (node (ref "Q4") (pin "2") (pinfunction "E_2") (pintype "passive"))
      (node (ref "Q5") (pin "2") (pinfunction "E_2") (pintype "passive"))
      (node (ref "Q6") (pin "2") (pinfunction "E_2") (pintype "passive"))
      (node (ref "Q7") (pin "2") (pinfunction "E_2") (pintype "passive"))
      (node (ref "Q8") (pin "2") (pinfunction "E_2") (pintype "passive"))
      (node (ref "R1") (pin "2") (pintype "passive"))
      (node (ref "R2") (pin "2") (pintype "passive"))
      (node (ref "R44") (pin "2") (pintype "passive"))
      (node (ref "R47") (pin "2") (pintype "passive"))
      (node (ref "R50") (pin "2") (pintype "passive"))
      (node (ref "R53") (pin "2") (pintype "passive"))
      (node (ref "R56") (pin "2") (pintype "passive"))
      (node (ref "R59") (pin "2") (pintype "passive"))
      (node (ref "R62") (pin "2") (pintype "passive"))
      (node (ref "R65") (pin "2") (pintype "passive"))
      (node (ref "U1") (pin "3") (pinfunction "GND_3") (pintype "passive"))
      (node (ref "U2") (pin "3") (pinfunction "GND_3") (pintype "passive"))
    )
    (net (code "36") (name "/I2C1-SCL") (class "Default")
      (node (ref "JP5") (pin "1") (pinfunction "1_1") (pintype "passive"))
      (node (ref "Pd") (pin "13") (pinfunction "13_13") (pintype "passive"))
    )
    (net (code "37") (name "/I2C1-SDA") (class "Default")
      (node (ref "JP5") (pin "3") (pinfunction "3_3") (pintype "passive"))
      (node (ref "Pd") (pin "14") (pinfunction "14_14") (pintype "passive"))
    )
    (net (code "38") (name "/ISN") (class "Default")
      (node (ref "JP3b") (pin "1") (pinfunction "1_1") (pintype "passive"))
      (node (ref "R13") (pin "1") (pintype "passive"))
    )
    (net (code "39") (name "/ISP") (class "Default")
      (node (ref "JP3b") (pin "3") (pinfunction "3_3") (pintype "passive"))
      (node (ref "R14") (pin "1") (pintype "passive"))
    )
    (net (code "40") (name "/K-R-A") (class "Default")
      (node (ref "Pc") (pin "9") (pinfunction "9_9") (pintype "passive+no_connect"))
    )
    (net (code "41") (name "/K-R-B") (class "Default")
      (node (ref "Pc") (pin "10") (pinfunction "10_10") (pintype "passive+no_connect"))
    )
    (net (code "42") (name "/KEY3-R") (class "Default")
      (node (ref "Pc") (pin "11") (pinfunction "11_11") (pintype "passive+no_connect"))
    )
    (net (code "43") (name "/KEY4") (class "Default")
      (node (ref "Pc") (pin "12") (pinfunction "12_12") (pintype "passive+no_connect"))
    )
    (net (code "44") (name "/KEY5") (class "Default")
      (node (ref "Pc") (pin "13") (pinfunction "13_13") (pintype "passive+no_connect"))
    )
    (net (code "45") (name "/KEY6") (class "Default")
      (node (ref "Pa") (pin "3") (pinfunction "3_3") (pintype "passive+no_connect"))
    )
    (net (code "46") (name "/LCD-D4") (class "Default")
      (node (ref "Pa") (pin "8") (pinfunction "8_8") (pintype "passive+no_connect"))
    )
    (net (code "47") (name "/LCD-D5") (class "Default")
      (node (ref "Pa") (pin "9") (pinfunction "9_9") (pintype "passive+no_connect"))
    )
    (net (code "48") (name "/LCD-D6") (class "Default")
      (node (ref "Pa") (pin "10") (pinfunction "10_10") (pintype "passive+no_connect"))
    )
    (net (code "49") (name "/LCD-D7") (class "Default")
      (node (ref "Pa") (pin "11") (pinfunction "11_11") (pintype "passive+no_connect"))
    )
    (net (code "50") (name "/LED1") (class "Default")
      (node (ref "Pd") (pin "3") (pinfunction "3_3") (pintype "passive+no_connect"))
    )
    (net (code "51") (name "/LED2") (class "Default")
      (node (ref "Pd") (pin "4") (pinfunction "4_4") (pintype "passive+no_connect"))
    )
    (net (code "52") (name "/LED3") (class "Default")
      (node (ref "Pd") (pin "5") (pinfunction "5_5") (pintype "passive+no_connect"))
    )
    (net (code "53") (name "/LED4") (class "Default")
      (node (ref "Pd") (pin "6") (pinfunction "6_6") (pintype "passive+no_connect"))
    )
    (net (code "55") (name "/NREF") (class "Default")
      (node (ref "CE7") (pin "2") (pintype "passive"))
      (node (ref "JP2") (pin "3") (pinfunction "3_3") (pintype "passive"))
      (node (ref "R12") (pin "2") (pintype "passive"))
      (node (ref "R18") (pin "2") (pintype "passive"))
      (node (ref "R6") (pin "1") (pintype "passive"))
      (node (ref "U4") (pin "1") (pintype "passive"))
    )
    (net (code "56") (name "/NTC1") (class "Default")
      (node (ref "JP11") (pin "1") (pinfunction "1_1") (pintype "passive"))
      (node (ref "R67") (pin "1") (pintype "passive"))
      (node (ref "R68") (pin "2") (pintype "passive"))
    )
    (net (code "57") (name "/NTC2") (class "Default")
      (node (ref "JP11") (pin "4") (pinfunction "4_4") (pintype "passive"))
      (node (ref "R69") (pin "1") (pintype "passive"))
      (node (ref "R78") (pin "2") (pintype "passive"))
    )
    (net (code "58") (name "/OP1A") (class "Default")
      (node (ref "JP7") (pin "1") (pinfunction "1_1") (pintype "passive"))
      (node (ref "R70") (pin "1") (pintype "passive"))
    )
    (net (code "59") (name "/OP1K") (class "Default")
      (node (ref "JP7") (pin "2") (pinfunction "2_2") (pintype "passive"))
      (node (ref "OP1") (pin "1") (pinfunction "A_1") (pintype "passive"))
    )
    (net (code "60") (name "/OP2A") (class "Default")
      (node (ref "JP7") (pin "3") (pinfunction "3_3") (pintype "passive"))
      (node (ref "R72") (pin "1") (pintype "passive"))
    )
    (net (code "61") (name "/OP2K") (class "Default")
      (node (ref "JP7") (pin "4") (pinfunction "4_4") (pintype "passive"))
      (node (ref "OP2") (pin "1") (pinfunction "A_1") (pintype "passive"))
    )
    (net (code "62") (name "/OP3A") (class "Default")
      (node (ref "JP7") (pin "5") (pinfunction "5_5") (pintype "passive"))
      (node (ref "R74") (pin "1") (pintype "passive"))
    )
    (net (code "63") (name "/OP3K") (class "Default")
      (node (ref "JP7") (pin "6") (pinfunction "6_6") (pintype "passive"))
      (node (ref "OP3") (pin "1") (pinfunction "A_1") (pintype "passive"))
    )
    (net (code "64") (name "/OP4A") (class "Default")
      (node (ref "JP7") (pin "7") (pinfunction "7_7") (pintype "passive"))
      (node (ref "R76") (pin "1") (pintype "passive"))
    )
    (net (code "65") (name "/OP4K") (class "Default")
      (node (ref "JP7") (pin "8") (pinfunction "8_8") (pintype "passive"))
      (node (ref "OP4") (pin "1") (pinfunction "A_1") (pintype "passive"))
    )
    (net (code "66") (name "/PA15") (class "Default")
      (node (ref "Pd") (pin "2") (pinfunction "2_2") (pintype "passive"))
      (node (ref "R55") (pin "1") (pintype "passive"))
    )
    (net (code "67") (name "/PB3") (class "Default")
      (node (ref "Pd") (pin "7") (pinfunction "7_7") (pintype "passive"))
      (node (ref "R58") (pin "1") (pintype "passive"))
    )
    (net (code "68") (name "/PB12") (class "Default")
      (node (ref "OP3") (pin "4") (pinfunction "E_4") (pintype "passive"))
      (node (ref "Pc") (pin "1") (pinfunction "1_1") (pintype "passive"))
      (node (ref "R75") (pin "1") (pintype "passive"))
    )
    (net (code "69") (name "/PB13") (class "Default")
      (node (ref "OP4") (pin "4") (pinfunction "E_4") (pintype "passive"))
      (node (ref "Pc") (pin "2") (pinfunction "2_2") (pintype "passive"))
      (node (ref "R77") (pin "1") (pintype "passive"))
    )
    (net (code "70") (name "/PB14") (class "Default")
      (node (ref "Pc") (pin "3") (pinfunction "3_3") (pintype "passive"))
      (node (ref "Q7") (pin "3") (pinfunction "C_3") (pintype "passive"))
      (node (ref "R63") (pin "2") (pintype "passive"))
    )
    (net (code "71") (name "/PB15") (class "Default")
      (node (ref "Pc") (pin "4") (pinfunction "4_4") (pintype "passive"))
      (node (ref "Q8") (pin "3") (pinfunction "C_3") (pintype "passive"))
      (node (ref "R66") (pin "2") (pintype "passive"))
    )
    (net (code "72") (name "/PC6") (class "Default")
      (node (ref "Pc") (pin "5") (pinfunction "5_5") (pintype "passive"))
      (node (ref "R43") (pin "1") (pintype "passive"))
    )
    (net (code "73") (name "/PC7") (class "Default")
      (node (ref "Pc") (pin "6") (pinfunction "6_6") (pintype "passive"))
      (node (ref "R46") (pin "1") (pintype "passive"))
    )
    (net (code "74") (name "/PC8") (class "Default")
      (node (ref "Pc") (pin "7") (pinfunction "7_7") (pintype "passive"))
      (node (ref "R49") (pin "1") (pintype "passive"))
    )
    (net (code "75") (name "/PC9") (class "Default")
      (node (ref "Pc") (pin "8") (pinfunction "8_8") (pintype "passive"))
      (node (ref "R52") (pin "1") (pintype "passive"))
    )
    (net (code "76") (name "/PREF") (class "Default")
      (node (ref "CE6") (pin "1") (pintype "passive"))
      (node (ref "JP2") (pin "1") (pinfunction "1_1") (pintype "passive"))
      (node (ref "R11") (pin "1") (pintype "passive"))
      (node (ref "R17") (pin "1") (pintype "passive"))
      (node (ref "R22") (pin "1") (pintype "passive"))
      (node (ref "R26") (pin "1") (pintype "passive"))
      (node (ref "R30") (pin "1") (pintype "passive"))
      (node (ref "R34") (pin "1") (pintype "passive"))
      (node (ref "R38") (pin "1") (pintype "passive"))
      (node (ref "R42") (pin "1") (pintype "passive"))
      (node (ref "R5") (pin "1") (pintype "passive"))
      (node (ref "R68") (pin "1") (pintype "passive"))
      (node (ref "R78") (pin "1") (pintype "passive"))
      (node (ref "U3") (pin "2") (pintype "passive"))
    )
    (net (code "77") (name "/Q1B") (class "Default")
      (node (ref "JP8") (pin "2") (pinfunction "2_2") (pintype "passive"))
      (node (ref "R61") (pin "1") (pintype "passive"))
    )
    (net (code "78") (name "/Q1C") (class "Default")
      (node (ref "JP9") (pin "2") (pinfunction "2_2") (pintype "passive"))
      (node (ref "R48") (pin "2") (pintype "passive"))
    )
    (net (code "79") (name "/Q2B") (class "Default")
      (node (ref "JP8") (pin "3") (pinfunction "3_3") (pintype "passive"))
      (node (ref "R64") (pin "1") (pintype "passive"))
    )
    (net (code "80") (name "/Q2C") (class "Default")
      (node (ref "JP9") (pin "3") (pinfunction "3_3") (pintype "passive"))
      (node (ref "R51") (pin "2") (pintype "passive"))
    )
    (net (code "81") (name "/Q3C") (class "Default")
      (node (ref "JP9") (pin "4") (pinfunction "4_4") (pintype "passive"))
      (node (ref "R45") (pin "2") (pintype "passive"))
    )
    (net (code "82") (name "/Q4C") (class "Default")
      (node (ref "JP9") (pin "5") (pinfunction "5_5") (pintype "passive"))
      (node (ref "R54") (pin "2") (pintype "passive"))
    )
    (net (code "83") (name "/Q5C") (class "Default")
      (node (ref "JP9") (pin "6") (pinfunction "6_6") (pintype "passive"))
      (node (ref "R57") (pin "2") (pintype "passive"))
    )
    (net (code "84") (name "/Q6C") (class "Default")
      (node (ref "JP9") (pin "7") (pinfunction "7_7") (pintype "passive"))
      (node (ref "R60") (pin "2") (pintype "passive"))
    )
    (net (code "85") (name "/REFa") (class "Default")
      (node (ref "C11") (pin "1") (pintype "passive"))
      (node (ref "POT2") (pin "3") (pintype "passive"))
      (node (ref "U5") (pin "5") (pinfunction "REF_5") (pintype "passive"))
    )
    (net (code "86") (name "/REFb") (class "Default")
      (node (ref "C18") (pin "1") (pintype "passive"))
      (node (ref "POT4") (pin "3") (pintype "passive"))
      (node (ref "U6") (pin "5") (pinfunction "REF_5") (pintype "passive"))
    )
    (net (code "87") (name "/RG1a") (class "Default")
      (node (ref "R9") (pin "1") (pintype "passive"))
      (node (ref "U5") (pin "1") (pinfunction "RG_1") (pintype "passive"))
    )
    (net (code "88") (name "/RG1b") (class "Default")
      (node (ref "R15") (pin "1") (pintype "passive"))
      (node (ref "U6") (pin "1") (pinfunction "RG_1") (pintype "passive"))
    )
    (net (code "89") (name "/RG2a") (class "Default")
      (node (ref "POT1") (pin "2") (pintype "passive"))
      (node (ref "POT1") (pin "3") (pintype "passive"))
      (node (ref "U5") (pin "8") (pinfunction "RG_8") (pintype "passive"))
    )
    (net (code "90") (name "/RG2b") (class "Default")
      (node (ref "POT3") (pin "2") (pintype "passive"))
      (node (ref "POT3") (pin "3") (pintype "passive"))
      (node (ref "U6") (pin "8") (pinfunction "RG_8") (pintype "passive"))
    )
    (net (code "91") (name "/RS") (class "Default")
      (node (ref "Pb") (pin "7") (pinfunction "7_7") (pintype "passive+no_connect"))
    )
    (net (code "92") (name "/SD-CLK") (class "Default")
      (node (ref "JP4") (pin "4") (pinfunction "4_4") (pintype "passive"))
      (node (ref "Pb") (pin "5") (pinfunction "5_5") (pintype "passive"))
    )
    (net (code "93") (name "/SD-DI") (class "Default")
      (node (ref "JP4") (pin "3") (pinfunction "3_3") (pintype "passive"))
      (node (ref "Pd") (pin "9") (pinfunction "9_9") (pintype "passive"))
    )
    (net (code "94") (name "/SD-DO") (class "Default")
      (node (ref "JP4") (pin "2") (pinfunction "2_2") (pintype "passive"))
      (node (ref "Pd") (pin "8") (pinfunction "8_8") (pintype "passive"))
    )
    (net (code "95") (name "/SWCLK") (class "Default")
      (node (ref "Pd") (pin "1") (pinfunction "1_1") (pintype "passive+no_connect"))
    )
    (net (code "96") (name "/SWDIO") (class "Default")
      (node (ref "Pc") (pin "14") (pinfunction "14_14") (pintype "passive+no_connect"))
    )
    (net (code "97") (name "/USART1-RX") (class "Default")
      (node (ref "JP6") (pin "3") (pinfunction "3_3") (pintype "passive"))
      (node (ref "Pd") (pin "11") (pinfunction "11_11") (pintype "passive"))
    )
    (net (code "98") (name "/USART1-TX") (class "Default")
      (node (ref "JP6") (pin "1") (pinfunction "1_1") (pintype "passive"))
      (node (ref "Pd") (pin "10") (pinfunction "10_10") (pintype "passive"))
    )
    (net (code "99") (name "/VDDA") (class "Default")
      (node (ref "Pa") (pin "13") (pinfunction "13_13") (pintype "passive+no_connect"))
    )
    (net (code "100") (name "/VSN") (class "Default")
      (node (ref "JP3a") (pin "1") (pinfunction "1_1") (pintype "passive"))
      (node (ref "R7") (pin "1") (pintype "passive"))
    )
    (net (code "101") (name "/VSP") (class "Default")
      (node (ref "JP3a") (pin "3") (pinfunction "3_3") (pintype "passive"))
      (node (ref "R8") (pin "1") (pintype "passive"))
    )
    (net (code "102") (name "/V_BAT") (class "Default")
      (node (ref "Pa") (pin "1") (pinfunction "1_1") (pintype "passive+no_connect"))
    )
    (net (code "103") (name "AGND") (class "Default")
      (node (ref "C10") (pin "2") (pintype "passive"))
      (node (ref "C11") (pin "2") (pintype "passive"))
      (node (ref "C12") (pin "2") (pintype "passive"))
      (node (ref "C14") (pin "2") (pintype "passive"))
      (node (ref "C15") (pin "1") (pintype "passive"))
      (node (ref "C16") (pin "2") (pintype "passive"))
      (node (ref "C17") (pin "2") (pintype "passive"))
      (node (ref "C18") (pin "2") (pintype "passive"))
      (node (ref "C19") (pin "2") (pintype "passive"))
      (node (ref "C20") (pin "2") (pintype "passive"))
      (node (ref "C21") (pin "2") (pintype "passive"))
      (node (ref "C22") (pin "2") (pintype "passive"))
      (node (ref "C23") (pin "2") (pintype "passive"))
      (node (ref "C24") (pin "2") (pintype "passive"))
      (node (ref "C5") (pin "2") (pintype "passive"))
      (node (ref "C7") (pin "2") (pintype "passive"))
      (node (ref "C8") (pin "1") (pintype "passive"))
      (node (ref "C9") (pin "2") (pintype "passive"))
      (node (ref "CE10") (pin "2") (pintype "passive"))
      (node (ref "CE11") (pin "1") (pintype "passive"))
      (node (ref "CE12") (pin "2") (pintype "passive"))
      (node (ref "CE13") (pin "2") (pintype "passive"))
      (node (ref "CE14") (pin "2") (pintype "passive"))
      (node (ref "CE15") (pin "2") (pintype "passive"))
      (node (ref "CE16") (pin "2") (pintype "passive"))
      (node (ref "CE17") (pin "2") (pintype "passive"))
      (node (ref "CE18") (pin "1") (pintype "passive"))
      (node (ref "CE19") (pin "1") (pintype "passive"))
      (node (ref "CE6") (pin "2") (pintype "passive"))
      (node (ref "CE7") (pin "1") (pintype "passive"))
      (node (ref "CE8") (pin "2") (pintype "passive"))
      (node (ref "CE9") (pin "1") (pintype "passive"))
      (node (ref "DZ1") (pin "1") (pinfunction "A_1") (pintype "passive"))
      (node (ref "DZ2") (pin "1") (pinfunction "A_1") (pintype "passive"))
      (node (ref "JP10") (pin "8") (pinfunction "8_8") (pintype "passive"))
      (node (ref "JP11") (pin "2") (pinfunction "2_2") (pintype "passive"))
      (node (ref "JP11") (pin "3") (pinfunction "3_3") (pintype "passive"))
      (node (ref "JP2") (pin "2") (pinfunction "2_2") (pintype "passive"))
      (node (ref "JP3a") (pin "2") (pinfunction "2_2") (pintype "passive"))
      (node (ref "JP3b") (pin "2") (pinfunction "2_2") (pintype "passive"))
      (node (ref "Pa") (pin "12") (pinfunction "12_12") (pintype "passive"))
      (node (ref "Pa") (pin "6") (pinfunction "6_6") (pintype "passive"))
      (node (ref "R20") (pin "1") (pintype "passive"))
      (node (ref "R24") (pin "1") (pintype "passive"))
      (node (ref "R28") (pin "1") (pintype "passive"))
      (node (ref "R32") (pin "1") (pintype "passive"))
      (node (ref "R36") (pin "1") (pintype "passive"))
      (node (ref "R40") (pin "1") (pintype "passive"))
      (node (ref "U3") (pin "1") (pintype "passive"))
      (node (ref "U4") (pin "2") (pintype "passive"))
    )
    (net (code "104") (name "Net-(C19-Pad1)") (class "Default")
      (node (ref "C19") (pin "1") (pintype "passive"))
      (node (ref "CE12") (pin "1") (pintype "passive"))
      (node (ref "R19") (pin "2") (pintype "passive"))
      (node (ref "R20") (pin "2") (pintype "passive"))
      (node (ref "R21") (pin "1") (pintype "passive"))
      (node (ref "R22") (pin "2") (pintype "passive"))
    )
    (net (code "105") (name "Net-(C20-Pad1)") (class "Default")
      (node (ref "C20") (pin "1") (pintype "passive"))
      (node (ref "CE13") (pin "1") (pintype "passive"))
      (node (ref "R23") (pin "2") (pintype "passive"))
      (node (ref "R24") (pin "2") (pintype "passive"))
      (node (ref "R25") (pin "1") (pintype "passive"))
      (node (ref "R26") (pin "2") (pintype "passive"))
    )
    (net (code "106") (name "Net-(C21-Pad1)") (class "Default")
      (node (ref "C21") (pin "1") (pintype "passive"))
      (node (ref "CE14") (pin "1") (pintype "passive"))
      (node (ref "R27") (pin "2") (pintype "passive"))
      (node (ref "R28") (pin "2") (pintype "passive"))
      (node (ref "R29") (pin "1") (pintype "passive"))
      (node (ref "R30") (pin "2") (pintype "passive"))
    )
    (net (code "107") (name "Net-(C22-Pad1)") (class "Default")
      (node (ref "C22") (pin "1") (pintype "passive"))
      (node (ref "CE15") (pin "1") (pintype "passive"))
      (node (ref "R31") (pin "2") (pintype "passive"))
      (node (ref "R32") (pin "2") (pintype "passive"))
      (node (ref "R33") (pin "1") (pintype "passive"))
      (node (ref "R34") (pin "2") (pintype "passive"))
    )
    (net (code "108") (name "Net-(C23-Pad1)") (class "Default")
      (node (ref "C23") (pin "1") (pintype "passive"))
      (node (ref "CE16") (pin "1") (pintype "passive"))
      (node (ref "R35") (pin "2") (pintype "passive"))
      (node (ref "R36") (pin "2") (pintype "passive"))
      (node (ref "R37") (pin "1") (pintype "passive"))
      (node (ref "R38") (pin "2") (pintype "passive"))
    )
    (net (code "109") (name "Net-(C24-Pad1)") (class "Default")
      (node (ref "C24") (pin "1") (pintype "passive"))
      (node (ref "CE17") (pin "1") (pintype "passive"))
      (node (ref "R39") (pin "2") (pintype "passive"))
      (node (ref "R40") (pin "2") (pintype "passive"))
      (node (ref "R41") (pin "1") (pintype "passive"))
      (node (ref "R42") (pin "2") (pintype "passive"))
    )
    (net (code "110") (name "Net-(D2-K)") (class "Default")
      (node (ref "D2") (pin "2") (pinfunction "K_2") (pintype "passive"))
      (node (ref "L1") (pin "2") (pinfunction "2_2") (pintype "passive"))
      (node (ref "U1") (pin "2") (pinfunction "OUT_2") (pintype "passive"))
    )
    (net (code "111") (name "Net-(LED1-A)") (class "Default")
      (node (ref "LED1") (pin "1") (pinfunction "A_1") (pintype "passive"))
      (node (ref "R4") (pin "2") (pintype "passive"))
    )
    (net (code "112") (name "Net-(OP1-K)") (class "Default")
      (node (ref "OP1") (pin "2") (pinfunction "K_2") (pintype "passive"))
      (node (ref "R70") (pin "2") (pintype "passive"))
    )
    (net (code "113") (name "Net-(OP2-K)") (class "Default")
      (node (ref "OP2") (pin "2") (pinfunction "K_2") (pintype "passive"))
      (node (ref "R72") (pin "2") (pintype "passive"))
    )
    (net (code "114") (name "Net-(OP3-K)") (class "Default")
      (node (ref "OP3") (pin "2") (pinfunction "K_2") (pintype "passive"))
      (node (ref "R74") (pin "2") (pintype "passive"))
    )
    (net (code "115") (name "Net-(OP4-K)") (class "Default")
      (node (ref "OP4") (pin "2") (pinfunction "K_2") (pintype "passive"))
      (node (ref "R76") (pin "2") (pintype "passive"))
    )
    (net (code "116") (name "Net-(POT1-Pad1)") (class "Default")
      (node (ref "POT1") (pin "1") (pintype "passive"))
      (node (ref "R9") (pin "2") (pintype "passive"))
    )
    (net (code "117") (name "Net-(POT2-Pad1)") (class "Default")
      (node (ref "POT2") (pin "1") (pintype "passive"))
      (node (ref "R11") (pin "2") (pintype "passive"))
    )
    (net (code "118") (name "Net-(POT2-Pad2)") (class "Default")
      (node (ref "POT2") (pin "2") (pintype "passive"))
      (node (ref "R12") (pin "1") (pintype "passive"))
    )
    (net (code "119") (name "Net-(POT3-Pad1)") (class "Default")
      (node (ref "POT3") (pin "1") (pintype "passive"))
      (node (ref "R15") (pin "2") (pintype "passive"))
    )
    (net (code "120") (name "Net-(POT4-Pad1)") (class "Default")
      (node (ref "POT4") (pin "1") (pintype "passive"))
      (node (ref "R17") (pin "2") (pintype "passive"))
    )
    (net (code "121") (name "Net-(POT4-Pad2)") (class "Default")
      (node (ref "POT4") (pin "2") (pintype "passive"))
      (node (ref "R18") (pin "1") (pintype "passive"))
    )
    (net (code "122") (name "Net-(Q1-B)") (class "Default")
      (node (ref "Q1") (pin "1") (pinfunction "B_1") (pintype "passive"))
      (node (ref "R43") (pin "2") (pintype "passive"))
      (node (ref "R44") (pin "1") (pintype "passive"))
    )
    (net (code "123") (name "Net-(Q1-C)") (class "Default")
      (node (ref "Q1") (pin "3") (pinfunction "C_3") (pintype "passive"))
      (node (ref "R45") (pin "1") (pintype "passive"))
    )
    (net (code "124") (name "Net-(Q2-B)") (class "Default")
      (node (ref "Q2") (pin "1") (pinfunction "B_1") (pintype "passive"))
      (node (ref "R46") (pin "2") (pintype "passive"))
      (node (ref "R47") (pin "1") (pintype "passive"))
    )
    (net (code "125") (name "Net-(Q2-C)") (class "Default")
      (node (ref "Q2") (pin "3") (pinfunction "C_3") (pintype "passive"))
      (node (ref "R48") (pin "1") (pintype "passive"))
    )
    (net (code "126") (name "Net-(Q3-B)") (class "Default")
      (node (ref "Q3") (pin "1") (pinfunction "B_1") (pintype "passive"))
      (node (ref "R49") (pin "2") (pintype "passive"))
      (node (ref "R50") (pin "1") (pintype "passive"))
    )
    (net (code "127") (name "Net-(Q3-C)") (class "Default")
      (node (ref "Q3") (pin "3") (pinfunction "C_3") (pintype "passive"))
      (node (ref "R51") (pin "1") (pintype "passive"))
    )
    (net (code "128") (name "Net-(Q4-B)") (class "Default")
      (node (ref "Q4") (pin "1") (pinfunction "B_1") (pintype "passive"))
      (node (ref "R52") (pin "2") (pintype "passive"))
      (node (ref "R53") (pin "1") (pintype "passive"))
    )
    (net (code "129") (name "Net-(Q4-C)") (class "Default")
      (node (ref "Q4") (pin "3") (pinfunction "C_3") (pintype "passive"))
      (node (ref "R54") (pin "1") (pintype "passive"))
    )
    (net (code "130") (name "Net-(Q5-B)") (class "Default")
      (node (ref "Q5") (pin "1") (pinfunction "B_1") (pintype "passive"))
      (node (ref "R55") (pin "2") (pintype "passive"))
      (node (ref "R56") (pin "1") (pintype "passive"))
    )
    (net (code "131") (name "Net-(Q5-C)") (class "Default")
      (node (ref "Q5") (pin "3") (pinfunction "C_3") (pintype "passive"))
      (node (ref "R57") (pin "1") (pintype "passive"))
    )
    (net (code "132") (name "Net-(Q6-B)") (class "Default")
      (node (ref "Q6") (pin "1") (pinfunction "B_1") (pintype "passive"))
      (node (ref "R58") (pin "2") (pintype "passive"))
      (node (ref "R59") (pin "1") (pintype "passive"))
    )
    (net (code "133") (name "Net-(Q6-C)") (class "Default")
      (node (ref "Q6") (pin "3") (pinfunction "C_3") (pintype "passive"))
      (node (ref "R60") (pin "1") (pintype "passive"))
    )
    (net (code "134") (name "Net-(Q7-B)") (class "Default")
      (node (ref "Q7") (pin "1") (pinfunction "B_1") (pintype "passive"))
      (node (ref "R61") (pin "2") (pintype "passive"))
      (node (ref "R62") (pin "1") (pintype "passive"))
    )
    (net (code "135") (name "Net-(Q8-B)") (class "Default")
      (node (ref "Q8") (pin "1") (pinfunction "B_1") (pintype "passive"))
      (node (ref "R64") (pin "2") (pintype "passive"))
      (node (ref "R65") (pin "1") (pintype "passive"))
    )
    (net (code "136") (name "Net-(U1-!ON{slash}OFF)") (class "Default")
      (node (ref "C2") (pin "2") (pintype "passive"))
      (node (ref "R1") (pin "1") (pintype "passive"))
      (node (ref "U1") (pin "5") (pinfunction "!ON/OFF_5") (pintype "passive"))
    )
    (net (code "137") (name "Net-(U1-FeedBack)") (class "Default")
      (node (ref "R2") (pin "1") (pintype "passive"))
      (node (ref "R3") (pin "2") (pintype "passive"))
      (node (ref "U1") (pin "4") (pinfunction "FeedBack_4") (pintype "passive"))
    )
    (net (code "138") (name "Net-(U2-CAP+)") (class "Default")
      (node (ref "CE5") (pin "1") (pintype "passive"))
      (node (ref "U2") (pin "2") (pinfunction "CAP+_2") (pintype "passive"))
    )
    (net (code "139") (name "Net-(U2-CAP-)") (class "Default")
      (node (ref "CE5") (pin "2") (pintype "passive"))
      (node (ref "U2") (pin "4") (pinfunction "CAP-_4") (pintype "passive"))
    )
    (net (code "140") (name "Net-(U2-Vout)") (class "Default")
      (node (ref "CE4") (pin "2") (pintype "passive"))
      (node (ref "L2") (pin "1") (pinfunction "1_1") (pintype "passive"))
      (node (ref "U2") (pin "5") (pinfunction "Vout_5") (pintype "passive"))
    )
    (net (code "141") (name "Net-(U5-OUT)") (class "Default")
      (node (ref "R10") (pin "2") (pintype "passive"))
      (node (ref "U5") (pin "6") (pinfunction "OUT_6") (pintype "passive"))
    )
    (net (code "142") (name "Net-(U6-OUT)") (class "Default")
      (node (ref "R16") (pin "2") (pintype "passive"))
      (node (ref "U6") (pin "6") (pinfunction "OUT_6") (pintype "passive"))
    )
    (net (code "143") (name "unconnected-(M1-Pad1)") (class "Default")
      (node (ref "M1") (pin "1") (pinfunction "1_1") (pintype "passive+no_connect"))
    )
    (net (code "144") (name "unconnected-(M2-Pad1)") (class "Default")
      (node (ref "M2") (pin "1") (pinfunction "1_1") (pintype "passive+no_connect"))
    )
    (net (code "145") (name "unconnected-(M3-Pad1)") (class "Default")
      (node (ref "M3") (pin "1") (pinfunction "1_1") (pintype "passive+no_connect"))
    )
    (net (code "146") (name "unconnected-(M4-Pad1)") (class "Default")
      (node (ref "M4") (pin "1") (pinfunction "1_1") (pintype "passive+no_connect"))
    )
    (net (code "147") (name "unconnected-(M5-Pad1)") (class "Default")
      (node (ref "M5") (pin "1") (pinfunction "1_1") (pintype "passive+no_connect"))
    )
    (net (code "148") (name "unconnected-(M6-Pad1)") (class "Default")
      (node (ref "M6") (pin "1") (pinfunction "1_1") (pintype "passive+no_connect"))
    )
    (net (code "149") (name "unconnected-(M7-Pad1)") (class "Default")
      (node (ref "M7") (pin "1") (pinfunction "1_1") (pintype "passive+no_connect"))
    )
    (net (code "150") (name "unconnected-(OP1-B-Pad6)") (class "Default")
      (node (ref "OP1") (pin "6") (pinfunction "B_6") (pintype "passive"))
    )
    (net (code "151") (name "unconnected-(OP1-NC-Pad3)") (class "Default")
      (node (ref "OP1") (pin "3") (pinfunction "NC_3") (pintype "passive"))
    )
    (net (code "152") (name "unconnected-(OP2-B-Pad6)") (class "Default")
      (node (ref "OP2") (pin "6") (pinfunction "B_6") (pintype "passive"))
    )
    (net (code "153") (name "unconnected-(OP2-NC-Pad3)") (class "Default")
      (node (ref "OP2") (pin "3") (pinfunction "NC_3") (pintype "passive"))
    )
    (net (code "154") (name "unconnected-(OP3-B-Pad6)") (class "Default")
      (node (ref "OP3") (pin "6") (pinfunction "B_6") (pintype "passive"))
    )
    (net (code "155") (name "unconnected-(OP3-NC-Pad3)") (class "Default")
      (node (ref "OP3") (pin "3") (pinfunction "NC_3") (pintype "passive"))
    )
    (net (code "156") (name "unconnected-(OP4-B-Pad6)") (class "Default")
      (node (ref "OP4") (pin "6") (pinfunction "B_6") (pintype "passive"))
    )
    (net (code "157") (name "unconnected-(OP4-NC-Pad3)") (class "Default")
      (node (ref "OP4") (pin "3") (pinfunction "NC_3") (pintype "passive"))
    )
    (net (code "158") (name "unconnected-(Pa-Pad7)") (class "Default")
      (node (ref "Pa") (pin "7") (pinfunction "7_7") (pintype "passive"))
    )
    (net (code "159") (name "unconnected-(Pd-Pad12)") (class "Default")
      (node (ref "Pd") (pin "12") (pinfunction "12_12") (pintype "passive+no_connect"))
    )
    (net (code "160") (name "unconnected-(U2-LV-Pad6)") (class "Default")
      (node (ref "U2") (pin "6") (pinfunction "LV_6") (pintype "passive"))
    )
    (net (code "161") (name "unconnected-(U2-OSC-Pad7)") (class "Default")
      (node (ref "U2") (pin "7") (pinfunction "OSC_7") (pintype "passive"))
    )
    (net (code "162") (name "unconnected-(U2-TEST-Pad1)") (class "Default")
      (node (ref "U2") (pin "1") (pinfunction "TEST_1") (pintype "passive"))
    )
    (net (code "163") (name "unconnected-(U3-Pad3)") (class "Default")
      (node (ref "U3") (pin "3") (pintype "passive+no_connect"))
    )
    (net (code "164") (name "unconnected-(U4-Pad3)") (class "Default")
      (node (ref "U4") (pin "3") (pintype "passive+no_connect"))
    )
  )
)
